# Hysteresis.net
KiCad netlist of a schematic drawn in EasyEDA
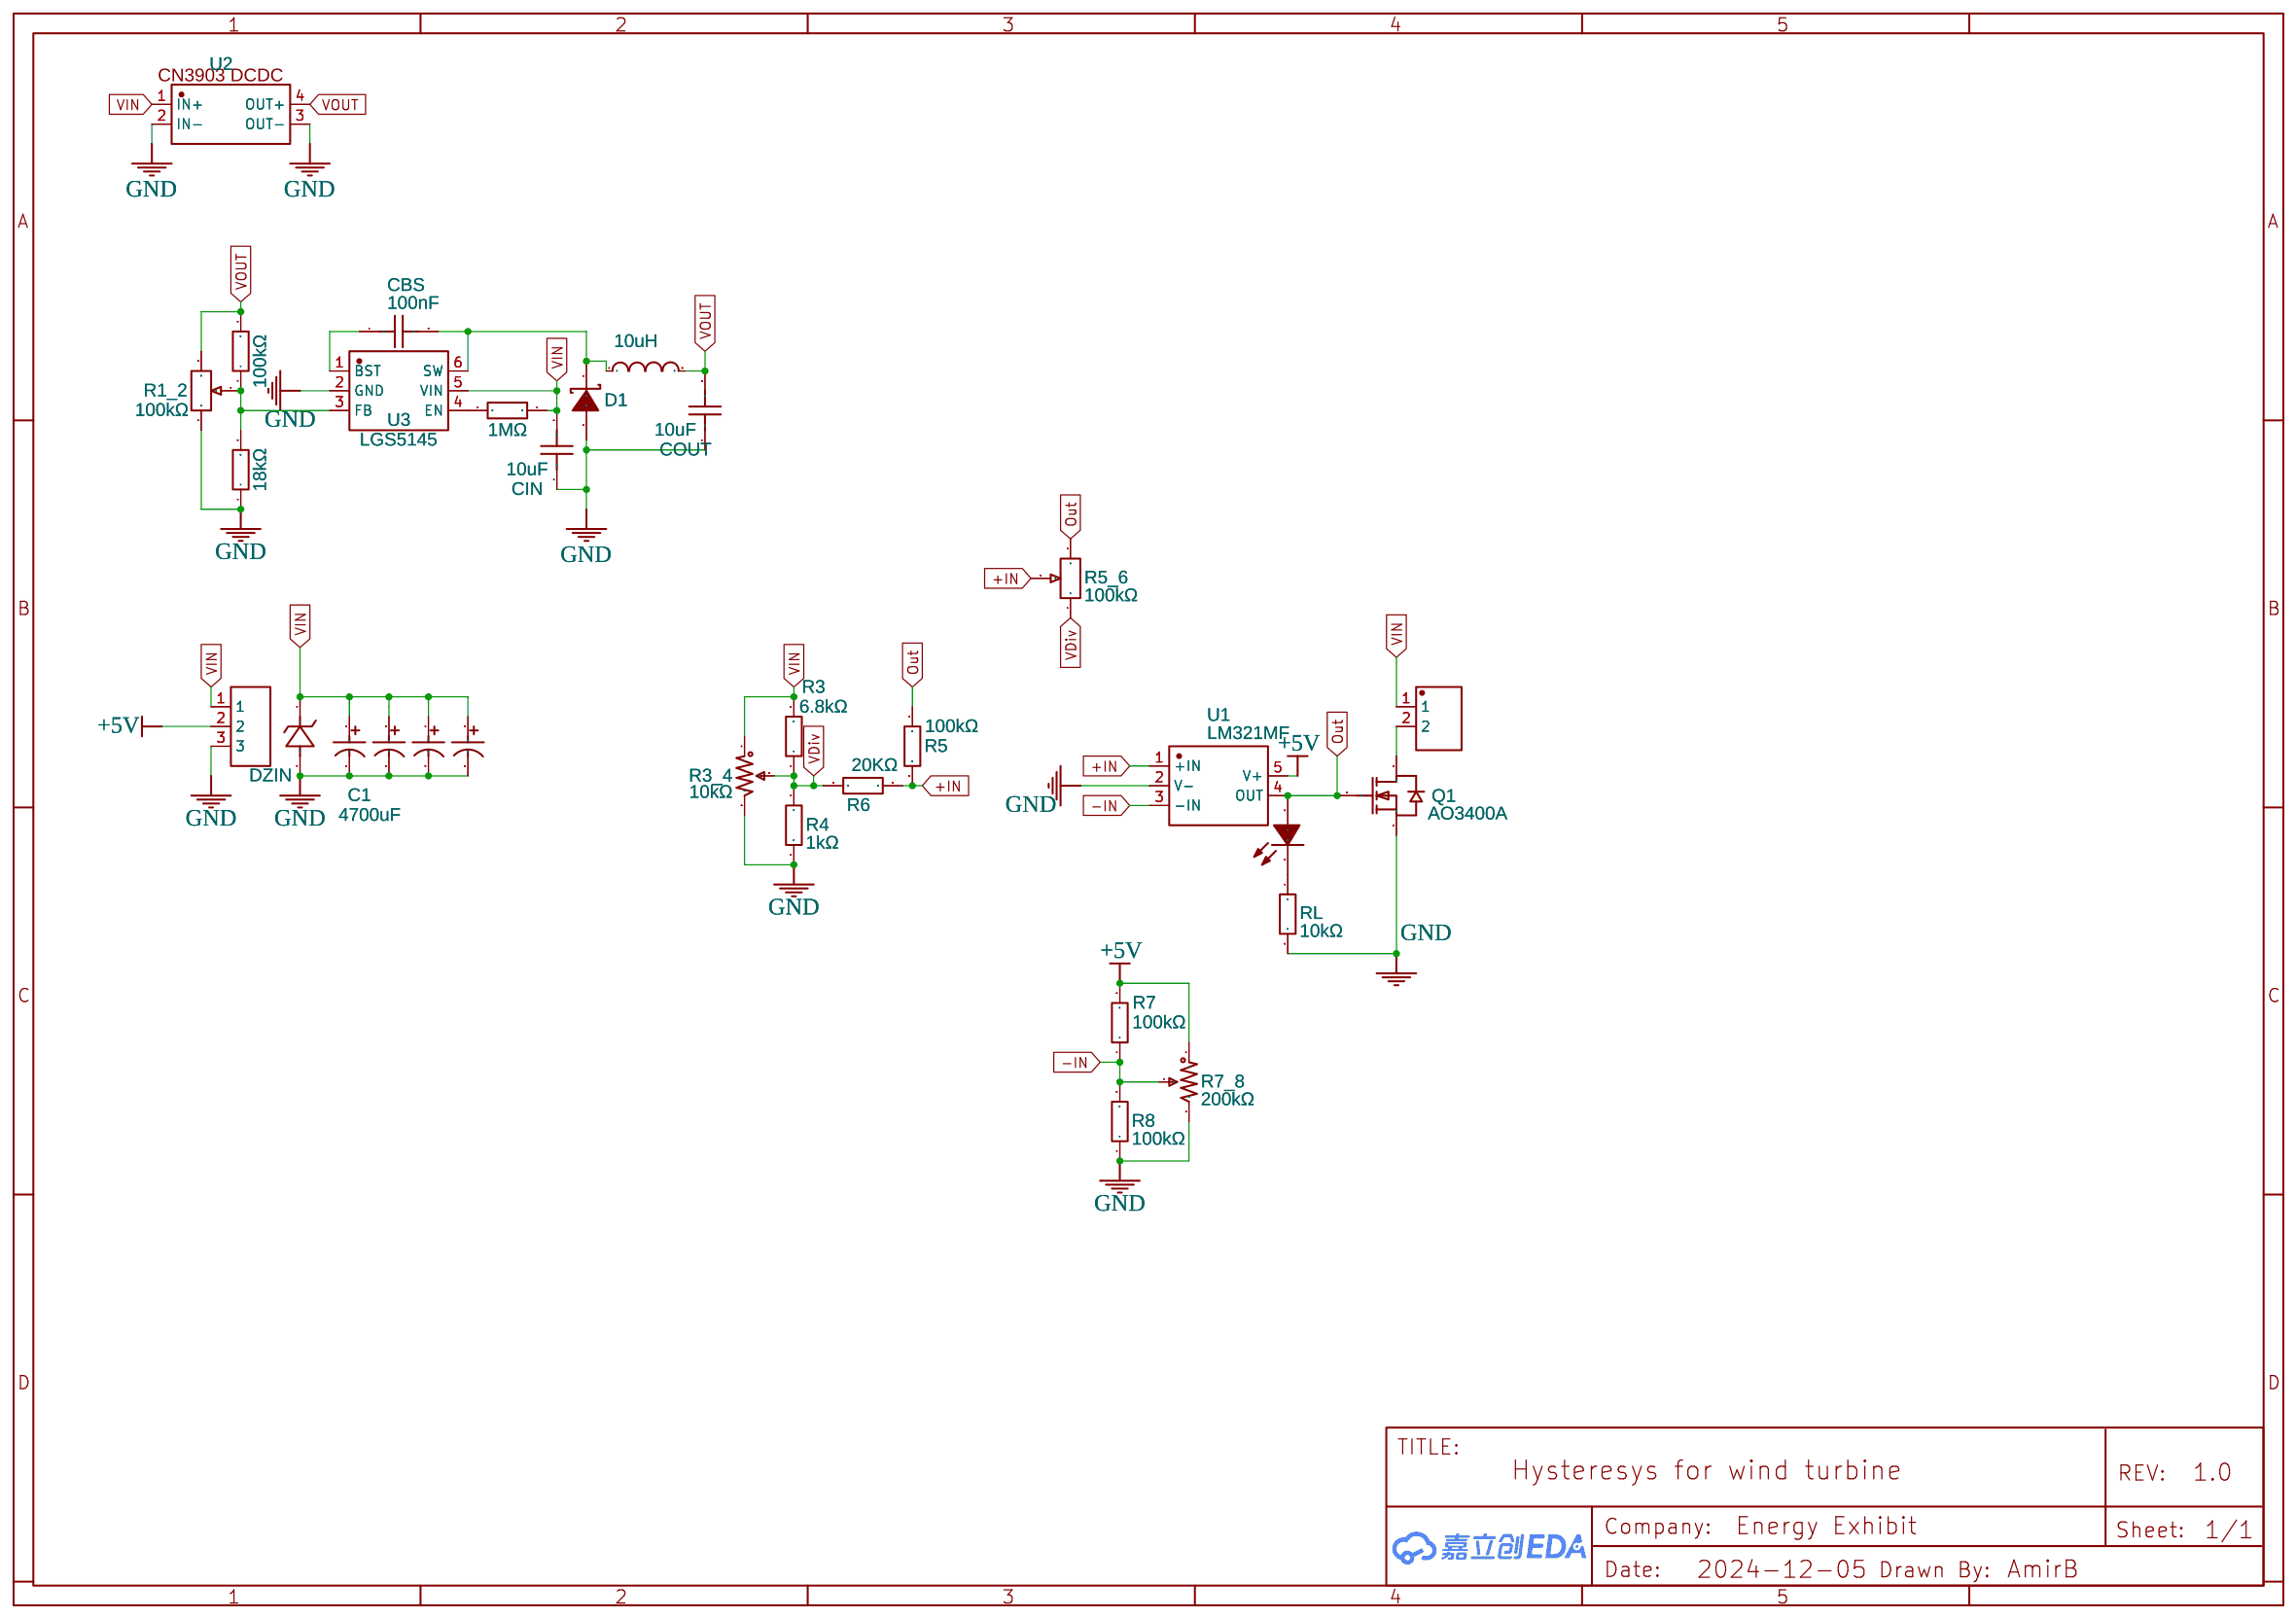
[diagram p0: schematic sheet]

(export (version "E")
  (design (tool "Eeschema 10.0.6"))
  (components
    (comp (ref "C1")
      (value "4700uF")
      (fields
        (field (name "Manufacturer Part") "KM478M035L30RR0VH2FP0")
        (field (name "Manufacturer") "CX(承兴)")
      )
      (libsource (lib "") (part "4700uF 35V 18*30"))
    )
    (comp (ref "C2")
      (value "4700uF")
      (fields
        (field (name "Manufacturer Part") "KM478M035L30RR0VH2FP0")
        (field (name "Manufacturer") "CX(承兴)")
      )
      (libsource (lib "") (part "4700uF 35V 18*30"))
    )
    (comp (ref "C3")
      (value "4700uF")
      (fields
        (field (name "Manufacturer Part") "KM478M035L30RR0VH2FP0")
        (field (name "Manufacturer") "CX(承兴)")
      )
      (libsource (lib "") (part "4700uF 35V 18*30"))
    )
    (comp (ref "C4")
      (value "4700uF")
      (fields
        (field (name "Manufacturer Part") "KM478M035L30RR0VH2FP0")
        (field (name "Manufacturer") "CX(承兴)")
      )
      (libsource (lib "") (part "4700uF 35V 18*30"))
    )
    (comp (ref "CBS")
      (value "100nF")
      (fields
        (field (name "Manufacturer Part") "CC0603KRX7R9BB104")
        (field (name "Manufacturer") "YAGEO(国巨)")
      )
      (libsource (lib "") (part "CC0603KRX7R9BB104"))
    )
    (comp (ref "CIN")
      (value "10uF")
      (fields
        (field (name "Manufacturer Part") "GRM21BR61H106KE43L")
        (field (name "Manufacturer") "muRata(村田)")
      )
      (libsource (lib "") (part "GRM21BR61H106KE43L"))
    )
    (comp (ref "CON_VIN")
      (value "FK2510")
      (fields (field (name "Manufacturer Part") "2510-3A") (field (name "Manufacturer") "BOOMELE(博穆精密)"))
      (libsource (lib "") (part "kf2510_3A"))
    )
    (comp (ref "COUT")
      (value "10uF")
      (fields
        (field (name "Manufacturer Part") "GRM21BR61H106KE43L")
        (field (name "Manufacturer") "muRata(村田)")
      )
      (libsource (lib "") (part "GRM21BR61H106KE43L_1"))
    )
    (comp (ref "D1")
      (value "SS210")
      (fields (field (name "Manufacturer") "MDD(辰达半导体)"))
      (libsource (lib "") (part "SS210"))
    )
    (comp (ref "DZIN")
      (value "SMBJ5361B")
      (fields (field (name "Manufacturer") "LGE(鲁光)"))
      (libsource (lib "") (part "SMBJ5361B"))
    )
    (comp (ref "L1")
      (value "10uH")
      (fields
        (field (name "Manufacturer Part") "MWSA0503S-100MT")
        (field (name "Manufacturer") "Sunlord(顺络)")
      )
      (libsource (lib "") (part "MWSA0503S-100MT"))
    )
    (comp (ref "LED")
      (value "KT-0603R")
      (fields (field (name "Manufacturer") "KENTO"))
      (libsource (lib "") (part "KT-0603R"))
    )
    (comp (ref "Q1")
      (value "AO3400A")
      (fields (field (name "Manufacturer") "AOS"))
      (libsource (lib "") (part "AO3400A"))
    )
    (comp (ref "R1")
      (value "100kΩ")
      (fields
        (field (name "Manufacturer Part") "0603WAF1003T5E")
        (field (name "Manufacturer") "UNI-ROYAL(厚声)")
      )
      (libsource (lib "") (part "0603WAF1003T5E"))
    )
    (comp (ref "R1_2")
      (value "100kΩ")
      (fields (field (name "Manufacturer Part") "3296W-1-104") (field (name "Manufacturer") "BOCHEN(博晨)"))
      (libsource (lib "") (part "3296W-1-104"))
    )
    (comp (ref "R2")
      (value "18kΩ")
      (fields
        (field (name "Manufacturer Part") "0603WAF1802T5E")
        (field (name "Manufacturer") "UNI-ROYAL(厚声)")
      )
      (libsource (lib "") (part "0603WAF1802T5E"))
    )
    (comp (ref "R3")
      (value "6.8kΩ")
      (fields
        (field (name "Manufacturer Part") "0603WAF6801T5E")
        (field (name "Manufacturer") "UNI-ROYAL(厚声)")
      )
      (libsource (lib "") (part "0603WAF6801T5E"))
    )
    (comp (ref "R3_4")
      (value "10kΩ")
      (fields (field (name "Manufacturer Part") "3296W-1-103") (field (name "Manufacturer") "BOCHEN(博晨)"))
      (libsource (lib "") (part "3296W-1-103"))
    )
    (comp (ref "R4")
      (value "1kΩ")
      (fields
        (field (name "Manufacturer Part") "0603WAF1001T5E")
        (field (name "Manufacturer") "UNI-ROYAL(厚声)")
      )
      (libsource (lib "") (part "0603WAF1001T5E"))
    )
    (comp (ref "R5")
      (value "100kΩ")
      (fields
        (field (name "Manufacturer Part") "0603WAF1003T5E")
        (field (name "Manufacturer") "UNI-ROYAL(厚声)")
      )
      (libsource (lib "") (part "0603WAF1003T5E_1"))
    )
    (comp (ref "R5_6")
      (value "100kΩ")
      (fields (field (name "Manufacturer Part") "3296W-1-104") (field (name "Manufacturer") "BOCHEN(博晨)"))
      (libsource (lib "") (part "3296W-1-104_1"))
    )
    (comp (ref "R6")
      (value "20KΩ")
      (fields
        (field (name "Manufacturer Part") "0603WAF200JT5E")
        (field (name "Manufacturer") "UNI-ROYAL(厚声)")
      )
      (libsource (lib "") (part "0603WAF200JT5E"))
    )
    (comp (ref "R7")
      (value "100kΩ")
      (fields
        (field (name "Manufacturer Part") "0603WAF1003T5E")
        (field (name "Manufacturer") "UNI-ROYAL(厚声)")
      )
      (libsource (lib "") (part "0603WAF1003T5E"))
    )
    (comp (ref "R7_8")
      (value "200kΩ")
      (fields (field (name "Manufacturer Part") "3296W-1-204") (field (name "Manufacturer") "BOCHEN(博晨)"))
      (libsource (lib "") (part "3296W-1-204"))
    )
    (comp (ref "R8")
      (value "100kΩ")
      (fields
        (field (name "Manufacturer Part") "0603WAF1003T5E")
        (field (name "Manufacturer") "UNI-ROYAL(厚声)")
      )
      (libsource (lib "") (part "0603WAF1003T5E"))
    )
    (comp (ref "REN")
      (value "1MΩ")
      (fields
        (field (name "Manufacturer Part") "0603WAF1004T5E")
        (field (name "Manufacturer") "UNI-ROYAL(厚声)")
      )
      (libsource (lib "") (part "0603WAF1004T5E"))
    )
    (comp (ref "RL")
      (value "10kΩ")
      (fields
        (field (name "BOM_Manufacturer Part") "0603WAF1002T5E")
        (field (name "BOM_Supplier Part") "C25804")
      )
      (libsource (lib "") (part "0603WAF1002T5E"))
    )
    (comp (ref "U1")
      (value "LM321MF")
      (fields (field (name "Manufacturer") "UMW(友台半导体)"))
      (libsource (lib "") (part "LM321MF"))
    )
    (comp (ref "U2")
      (value "CN3903-DCDC-STEPDOWN-3V3")
      (libsource (lib "") (part "CN3903-DCDC-STEPDOWN-3V3"))
    )
    (comp (ref "U3")
      (value "LGS5145")
      (fields (field (name "Manufacturer") "Legend-Si(棱晶半导体)"))
      (libsource (lib "") (part "LGS5145"))
    )
    (comp (ref "VHYS")
      (value "KF2510-2A")
      (fields (field (name "BOM_Supplier Part") "C27543"))
      (libsource (lib "") (part "KF2510-2A"))
    )
  )
  (nets
    (net (code "1") (name "+5V") (class "Default")
      (node (ref "CON_VIN") (pin "2") (pinfunction "2_2") (pintype "unspecified"))
      (node (ref "R7") (pin "2") (pinfunction "2_2") (pintype "input"))
      (node (ref "R7_8") (pin "1") (pinfunction "1_1") (pintype "unspecified"))
      (node (ref "U1") (pin "5") (pinfunction "V+_5") (pintype "unspecified"))
    )
    (net (code "2") (name "+IN") (class "Default")
      (node (ref "R5") (pin "2") (pinfunction "2_2") (pintype "input"))
      (node (ref "R5_6") (pin "2") (pinfunction "2_2") (pintype "input"))
      (node (ref "R6") (pin "2") (pinfunction "2_2") (pintype "input"))
      (node (ref "U1") (pin "1") (pinfunction "+IN_1") (pintype "unspecified"))
    )
    (net (code "3") (name "-IN") (class "Default")
      (node (ref "R7") (pin "1") (pinfunction "1_1") (pintype "input"))
      (node (ref "R7_8") (pin "2") (pinfunction "2_2") (pintype "unspecified"))
      (node (ref "R8") (pin "2") (pinfunction "2_2") (pintype "input"))
      (node (ref "U1") (pin "3") (pinfunction "-IN_3") (pintype "unspecified"))
    )
    (net (code "4") (name "GND") (class "Default")
      (node (ref "C1") (pin "2") (pinfunction "2_2") (pintype "input"))
      (node (ref "C2") (pin "2") (pinfunction "2_2") (pintype "input"))
      (node (ref "C3") (pin "2") (pinfunction "2_2") (pintype "input"))
      (node (ref "C4") (pin "2") (pinfunction "2_2") (pintype "input"))
      (node (ref "CIN") (pin "1") (pinfunction "1_1") (pintype "unspecified"))
      (node (ref "CON_VIN") (pin "3") (pinfunction "3_3") (pintype "unspecified"))
      (node (ref "COUT") (pin "1") (pinfunction "1_1") (pintype "unspecified"))
      (node (ref "D1") (pin "2") (pinfunction "A_2") (pintype "unspecified"))
      (node (ref "DZIN") (pin "2") (pinfunction "A_2") (pintype "unspecified"))
      (node (ref "Q1") (pin "2") (pinfunction "S_2") (pintype "unspecified"))
      (node (ref "R1_2") (pin "1") (pinfunction "1_1") (pintype "input"))
      (node (ref "R2") (pin "1") (pinfunction "1_1") (pintype "input"))
      (node (ref "R3_4") (pin "3") (pinfunction "3_3") (pintype "unspecified"))
      (node (ref "R4") (pin "1") (pinfunction "1_1") (pintype "input"))
      (node (ref "R7_8") (pin "3") (pinfunction "3_3") (pintype "unspecified"))
      (node (ref "R8") (pin "1") (pinfunction "1_1") (pintype "input"))
      (node (ref "RL") (pin "2") (pinfunction "2_2") (pintype "input"))
      (node (ref "U1") (pin "2") (pinfunction "V-_2") (pintype "unspecified"))
      (node (ref "U2") (pin "2") (pinfunction "IN-_2") (pintype "unspecified"))
      (node (ref "U2") (pin "3") (pinfunction "OUT-_3") (pintype "unspecified"))
      (node (ref "U3") (pin "2") (pinfunction "GND_2") (pintype "unspecified"))
    )
    (net (code "5") (name "Net-(D1-K)") (class "Default")
      (node (ref "CBS") (pin "2") (pinfunction "2_2") (pintype "unspecified"))
      (node (ref "D1") (pin "1") (pinfunction "K_1") (pintype "unspecified"))
      (node (ref "L1") (pin "1") (pinfunction "1_1") (pintype "unspecified"))
      (node (ref "U3") (pin "6") (pinfunction "SW_6") (pintype "unspecified"))
    )
    (net (code "6") (name "Net-(LED-K)") (class "Default")
      (node (ref "LED") (pin "1") (pinfunction "K_1") (pintype "unspecified"))
      (node (ref "RL") (pin "1") (pinfunction "1_1") (pintype "input"))
    )
    (net (code "7") (name "Net-(Q1-D)") (class "Default")
      (node (ref "Q1") (pin "3") (pinfunction "D_3") (pintype "unspecified"))
      (node (ref "VHYS") (pin "2") (pinfunction "2_2") (pintype "unspecified"))
    )
    (net (code "8") (name "Net-(U3-BST)") (class "Default")
      (node (ref "CBS") (pin "1") (pinfunction "1_1") (pintype "unspecified"))
      (node (ref "U3") (pin "1") (pinfunction "BST_1") (pintype "unspecified"))
    )
    (net (code "9") (name "Net-(U3-EN)") (class "Default")
      (node (ref "REN") (pin "2") (pinfunction "2_2") (pintype "input"))
      (node (ref "U3") (pin "4") (pinfunction "EN_4") (pintype "unspecified"))
    )
    (net (code "10") (name "Net-(U3-FB)") (class "Default")
      (node (ref "R1") (pin "1") (pinfunction "1_1") (pintype "input"))
      (node (ref "R1_2") (pin "2") (pinfunction "2_2") (pintype "input"))
      (node (ref "R2") (pin "2") (pinfunction "2_2") (pintype "input"))
      (node (ref "U3") (pin "3") (pinfunction "FB_3") (pintype "unspecified"))
    )
    (net (code "11") (name "Out") (class "Default")
      (node (ref "LED") (pin "2") (pinfunction "A_2") (pintype "unspecified"))
      (node (ref "Q1") (pin "1") (pinfunction "G_1") (pintype "unspecified"))
      (node (ref "R5") (pin "1") (pinfunction "1_1") (pintype "input"))
      (node (ref "R5_6") (pin "3") (pinfunction "3_3") (pintype "input"))
      (node (ref "U1") (pin "4") (pinfunction "OUT_4") (pintype "unspecified"))
    )
    (net (code "12") (name "VDiv") (class "Default")
      (node (ref "R3") (pin "1") (pinfunction "1_1") (pintype "input"))
      (node (ref "R3_4") (pin "2") (pinfunction "2_2") (pintype "unspecified"))
      (node (ref "R4") (pin "2") (pinfunction "2_2") (pintype "input"))
      (node (ref "R5_6") (pin "1") (pinfunction "1_1") (pintype "input"))
      (node (ref "R6") (pin "1") (pinfunction "1_1") (pintype "input"))
    )
    (net (code "13") (name "VIN") (class "Default")
      (node (ref "C1") (pin "1") (pinfunction "1_1") (pintype "input"))
      (node (ref "C2") (pin "1") (pinfunction "1_1") (pintype "input"))
      (node (ref "C3") (pin "1") (pinfunction "1_1") (pintype "input"))
      (node (ref "C4") (pin "1") (pinfunction "1_1") (pintype "input"))
      (node (ref "CIN") (pin "2") (pinfunction "2_2") (pintype "unspecified"))
      (node (ref "CON_VIN") (pin "1") (pinfunction "1_1") (pintype "unspecified"))
      (node (ref "DZIN") (pin "1") (pinfunction "K_1") (pintype "unspecified"))
      (node (ref "R3") (pin "2") (pinfunction "2_2") (pintype "input"))
      (node (ref "R3_4") (pin "1") (pinfunction "1_1") (pintype "unspecified"))
      (node (ref "REN") (pin "1") (pinfunction "1_1") (pintype "input"))
      (node (ref "U2") (pin "1") (pinfunction "IN+_1") (pintype "unspecified"))
      (node (ref "U3") (pin "5") (pinfunction "VIN_5") (pintype "unspecified"))
      (node (ref "VHYS") (pin "1") (pinfunction "1_1") (pintype "unspecified"))
    )
    (net (code "14") (name "VOUT") (class "Default")
      (node (ref "COUT") (pin "2") (pinfunction "2_2") (pintype "unspecified"))
      (node (ref "L1") (pin "2") (pinfunction "2_2") (pintype "unspecified"))
      (node (ref "R1") (pin "2") (pinfunction "2_2") (pintype "input"))
      (node (ref "R1_2") (pin "3") (pinfunction "3_3") (pintype "input"))
      (node (ref "U2") (pin "4") (pinfunction "OUT+_4") (pintype "unspecified"))
    )
  )
)
